# LP2985-33.net
KiCad netlist of a schematic drawn in EAGLE
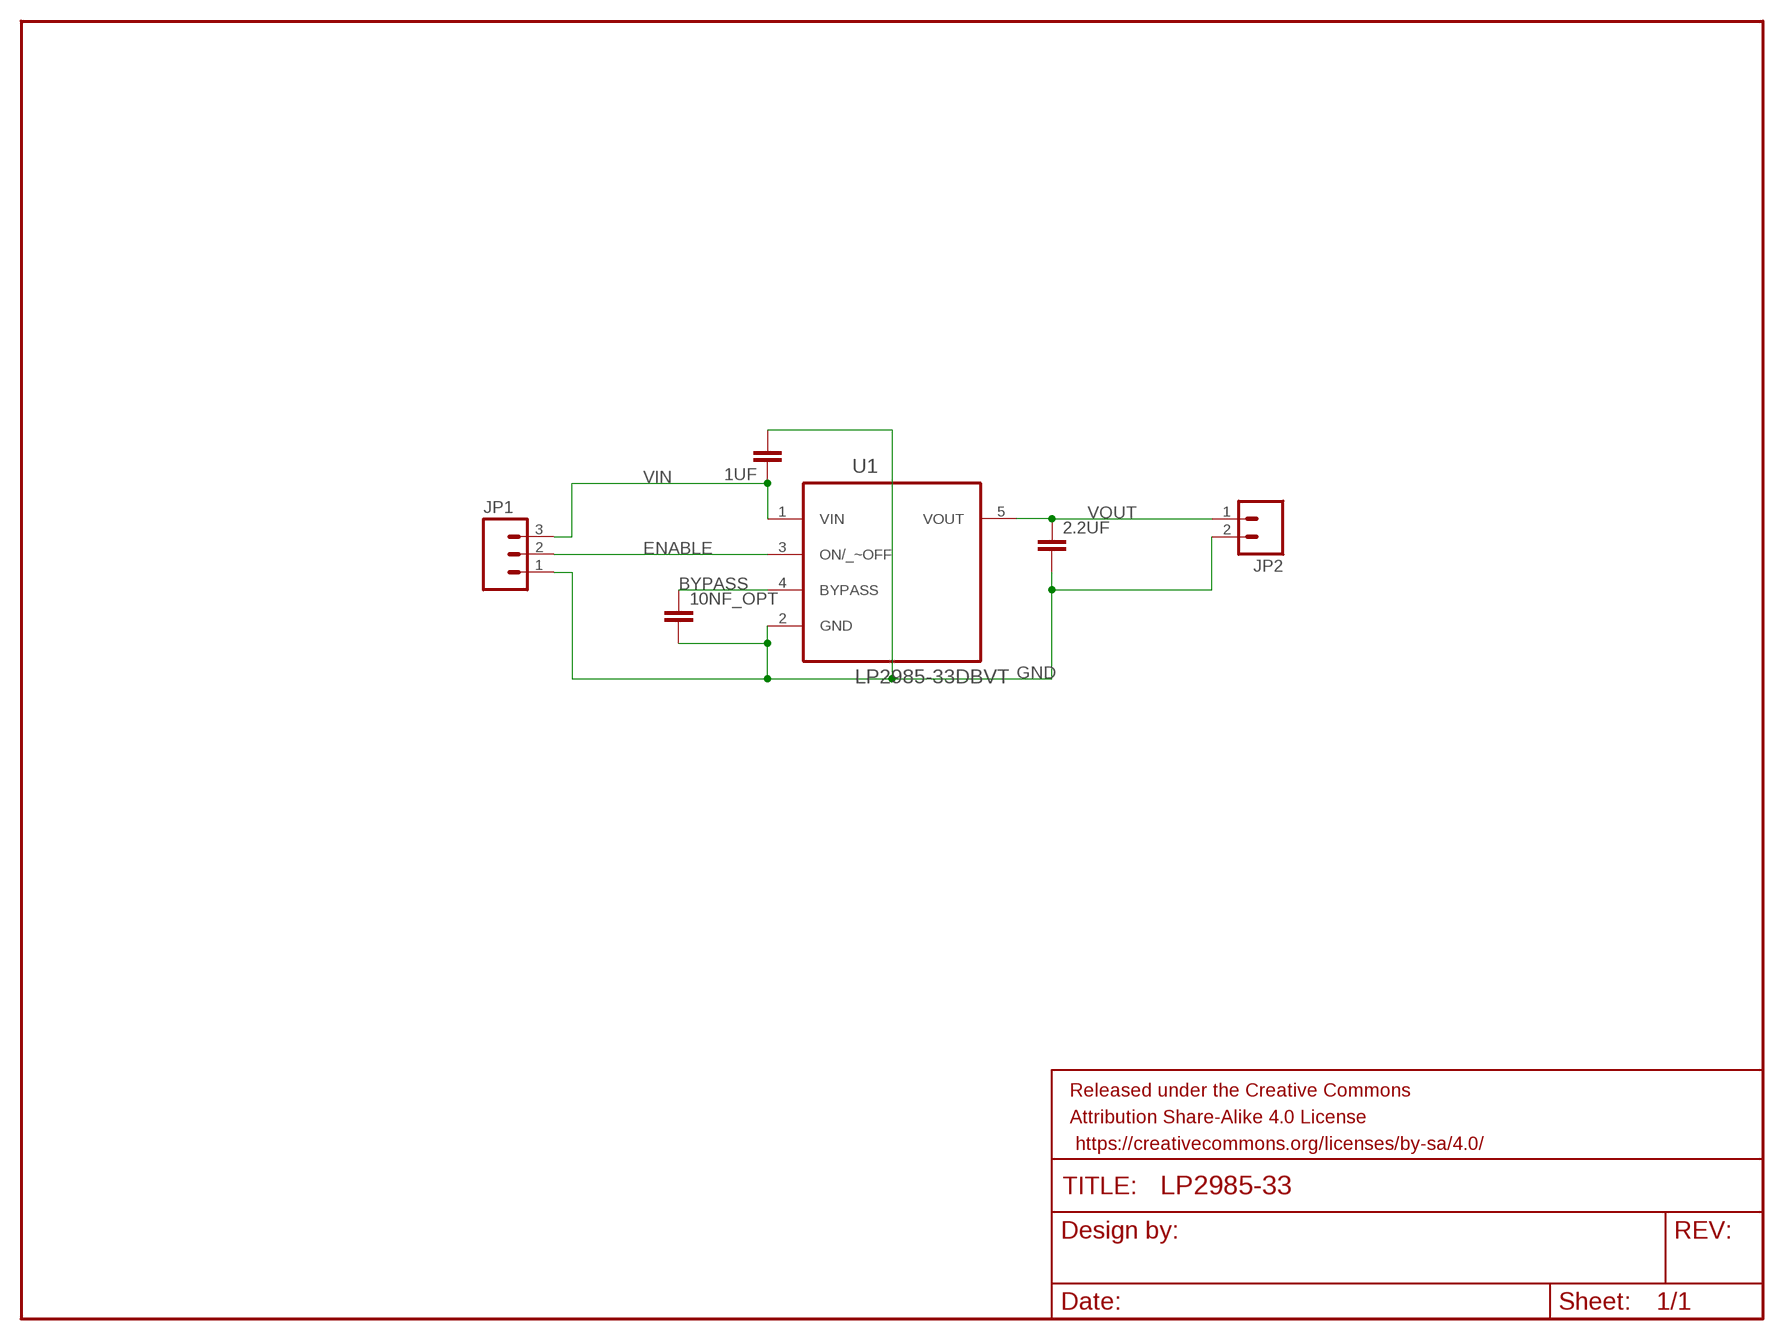
[diagram p0: schematic, sheet 1]

(export (version "E")
  (design (tool "Eeschema 10.0.6"))
  (components
    (comp (ref "1UF")
      (value "CAP0603-CAP")
      (footprint "eagle-import:0603-CAP")
      (libsource (lib "eagle-import") (part "CAP0603-CAP"))
    )
    (comp (ref "2.2UF")
      (value "CAP0603-CAP")
      (footprint "eagle-import:0603-CAP")
      (libsource (lib "eagle-import") (part "CAP0603-CAP"))
    )
    (comp (ref "10NF_OPT")
      (value "CAP0603-CAP")
      (footprint "eagle-import:0603-CAP")
      (libsource (lib "eagle-import") (part "CAP0603-CAP"))
    )
    (comp (ref "FRAME1")
      (value "FRAME-LETTER")
      (footprint "eagle-import:CREATIVE_COMMONS")
      (libsource (lib "eagle-import") (part "FRAME-LETTER"))
    )
    (comp (ref "JP1")
      (value "M03PTH")
      (footprint "eagle-import:1X03")
      (libsource (lib "eagle-import") (part "M03PTH"))
    )
    (comp (ref "JP2")
      (value "M02PTH")
      (footprint "eagle-import:1X02")
      (libsource (lib "eagle-import") (part "M02PTH"))
    )
    (comp (ref "U1")
      (value "LP2985-33DBVT")
      (footprint "eagle-import:SOT95P280X145-5N")
      (fields (field (name "MF") "Texas Instruments"))
      (libsource (lib "eagle-import") (part "LP2985-33DBVT"))
    )
  )
  (nets
    (net (code "1") (name "/BYPASS") (class "Default")
      (node (ref "10NF_OPT") (pin "1") (pinfunction "1_1") (pintype "passive"))
      (node (ref "U1") (pin "4") (pinfunction "BYPASS_4") (pintype "input"))
    )
    (net (code "2") (name "/ENABLE") (class "Default")
      (node (ref "JP1") (pin "2") (pinfunction "2_2") (pintype "passive"))
      (node (ref "U1") (pin "3") (pinfunction "ON/_~{OFF}_3") (pintype "input"))
    )
    (net (code "3") (name "/GND") (class "Default")
      (node (ref "10NF_OPT") (pin "2") (pinfunction "2_2") (pintype "passive"))
      (node (ref "1UF") (pin "2") (pinfunction "2_2") (pintype "passive"))
      (node (ref "2.2UF") (pin "2") (pinfunction "2_2") (pintype "passive"))
      (node (ref "JP1") (pin "1") (pinfunction "1_1") (pintype "passive"))
      (node (ref "JP2") (pin "2") (pinfunction "2_2") (pintype "passive"))
      (node (ref "U1") (pin "2") (pinfunction "GND_2") (pintype "passive"))
    )
    (net (code "4") (name "/VIN") (class "Default")
      (node (ref "1UF") (pin "1") (pinfunction "1_1") (pintype "passive"))
      (node (ref "JP1") (pin "3") (pinfunction "3_3") (pintype "passive"))
      (node (ref "U1") (pin "1") (pinfunction "VIN_1") (pintype "power_in"))
    )
    (net (code "5") (name "/VOUT") (class "Default")
      (node (ref "2.2UF") (pin "1") (pinfunction "1_1") (pintype "passive"))
      (node (ref "JP2") (pin "1") (pinfunction "1_1") (pintype "passive"))
      (node (ref "U1") (pin "5") (pinfunction "VOUT_5") (pintype "output"))
    )
  )
)
